# Circuit_comp.net
KiCad netlist of a schematic drawn in Altium Designer
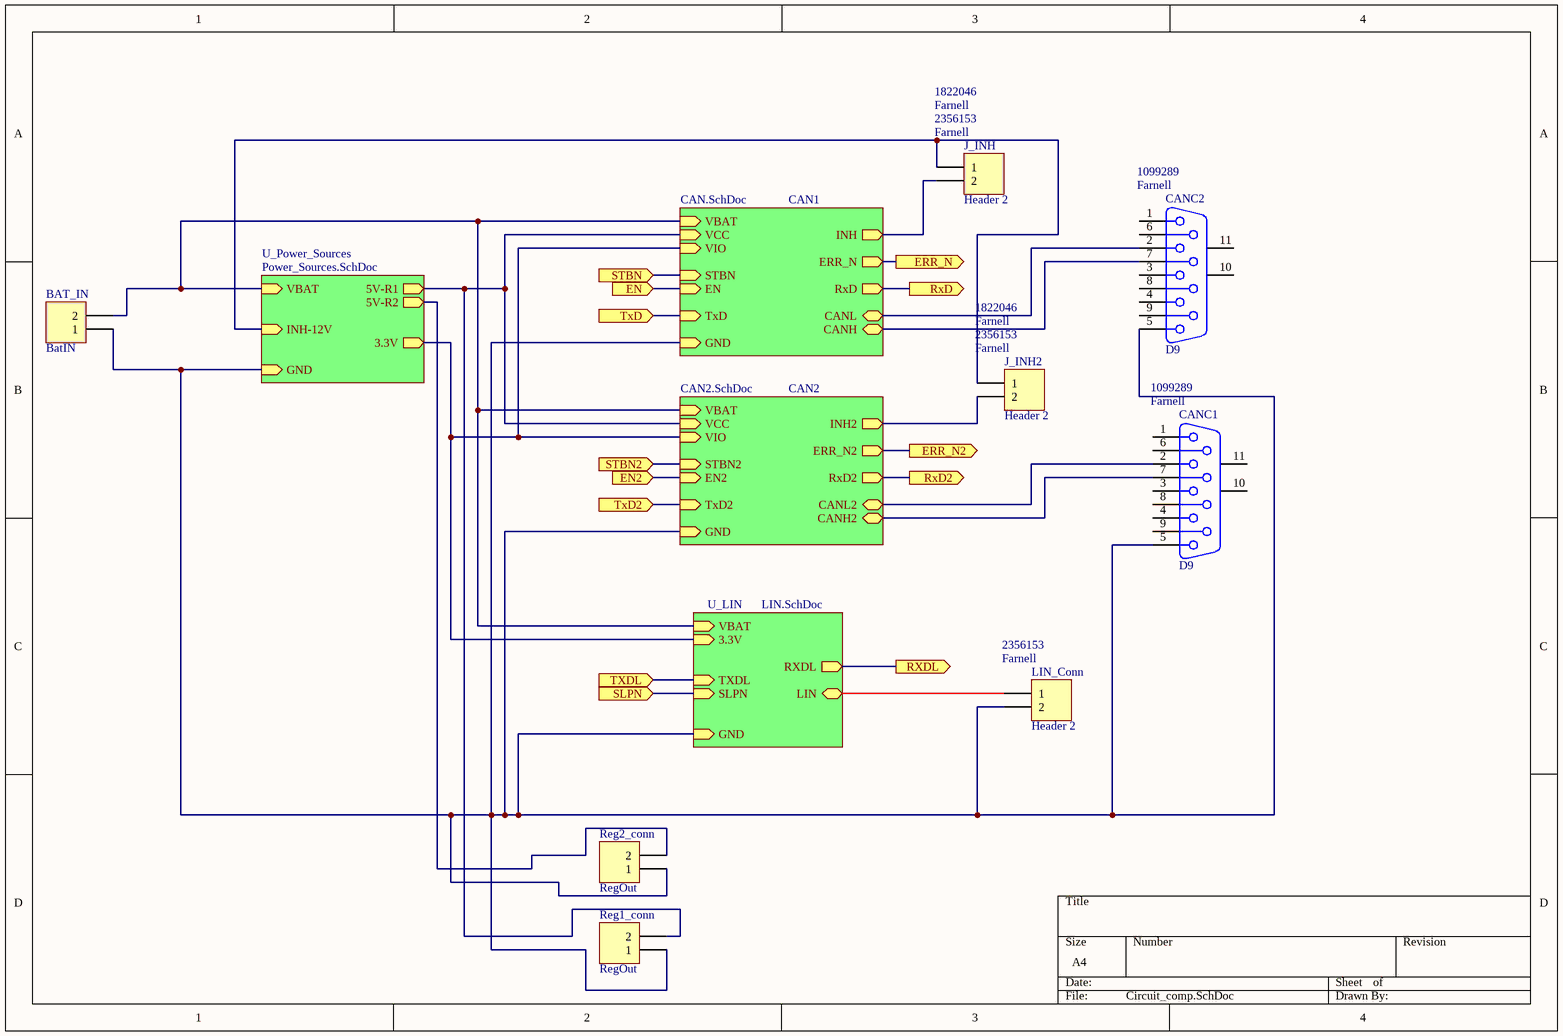
[diagram p0: Circuit_comp.SchDoc]

(export (version "E")
  (design (tool "Eeschema 10.0.6"))
  (components
    (comp (ref "BAT_IN")
      (value "BatIN")
      (footprint "HDR1X2")
      (description "Header, 2-Pin")
      (fields (field (name "PUBLISHER") "Altium Limited"))
      (libsource (lib "") (part "Header 2_1"))
    )
    (comp (ref "CANC1")
      (value "D9")
      (footprint "DSUB1.385-2H9")
      (description "Receptacle Assembly, 9 Position, Right Angle")
      (fields
        (field (name "SUPPLIER 1") "Farnell")
        (field (name "SUPPLIER PART NUMBER 1") "1099289")
        (field (name "PUBLISHER") "Altium Limited")
      )
      (libsource (lib "Miscellaneous Connectors") (part "D Connector 9"))
    )
    (comp (ref "CANC2")
      (value "D9")
      (footprint "DSUB1.385-2H9")
      (description "Receptacle Assembly, 9 Position, Right Angle")
      (fields
        (field (name "SUPPLIER 1") "Farnell")
        (field (name "SUPPLIER PART NUMBER 1") "1099289")
        (field (name "PUBLISHER") "Altium Limited")
      )
      (libsource (lib "Miscellaneous Connectors") (part "D Connector 9"))
    )
    (comp (ref "J_INH")
      (value "Header 2")
      (footprint "HDR1X2")
      (description "Header, 2-Pin")
      (fields
        (field (name "SUPPLIER 1") "Farnell")
        (field (name "SUPPLIER PART NUMBER 1") "2356153")
        (field (name "SUPPLIER 2") "Farnell")
        (field (name "SUPPLIER PART NUMBER 2") "1822046")
        (field (name "PUBLISHER") "Altium Limited")
      )
      (libsource (lib "Miscellaneous Connectors") (part "Header 2"))
    )
    (comp (ref "J_INH2")
      (value "Header 2")
      (footprint "HDR1X2")
      (description "Header, 2-Pin")
      (fields
        (field (name "SUPPLIER 1") "Farnell")
        (field (name "SUPPLIER PART NUMBER 1") "2356153")
        (field (name "SUPPLIER 2") "Farnell")
        (field (name "SUPPLIER PART NUMBER 2") "1822046")
        (field (name "PUBLISHER") "Altium Limited")
      )
      (libsource (lib "Miscellaneous Connectors") (part "Header 2"))
    )
    (comp (ref "LIN_Conn")
      (value "Header 2")
      (footprint "HDR1X2")
      (description "Header, 2-Pin")
      (fields
        (field (name "SUPPLIER 1") "Farnell")
        (field (name "SUPPLIER PART NUMBER 1") "2356153")
        (field (name "PUBLISHER") "Altium Limited")
      )
      (libsource (lib "Miscellaneous Connectors") (part "Header 2"))
    )
    (comp (ref "Reg1_conn")
      (value "RegOut")
      (footprint "HDR1X2")
      (description "Header, 2-Pin")
      (fields (field (name "PUBLISHER") "Altium Limited"))
      (libsource (lib "") (part "Header 2_1"))
    )
    (comp (ref "Reg2_conn")
      (value "RegOut")
      (footprint "HDR1X2")
      (description "Header, 2-Pin")
      (fields (field (name "PUBLISHER") "Altium Limited"))
      (libsource (lib "") (part "Header 2_1"))
    )
  )
  (nets
    (net (code "2") (name "/5V-R1") (class "Default")
      (node (ref "Reg1_conn") (pin "2") (pinfunction "2_2") (pintype "passive"))
    )
    (net (code "3") (name "/5V-R2") (class "Default")
      (node (ref "Reg2_conn") (pin "2") (pinfunction "2_2") (pintype "passive"))
    )
    (net (code "4") (name "/CANH") (class "Default")
      (node (ref "CANC2") (pin "7") (pinfunction "7_7") (pintype "passive"))
    )
    (net (code "5") (name "/CANH2") (class "Default")
      (node (ref "CANC1") (pin "7") (pinfunction "7_7") (pintype "passive"))
    )
    (net (code "6") (name "/CANL") (class "Default")
      (node (ref "CANC2") (pin "2") (pinfunction "2_2") (pintype "passive"))
    )
    (net (code "7") (name "/CANL2") (class "Default")
      (node (ref "CANC1") (pin "2") (pinfunction "2_2") (pintype "passive"))
    )
    (net (code "12") (name "/GND") (class "Default")
      (node (ref "BAT_IN") (pin "1") (pinfunction "1_1") (pintype "passive"))
      (node (ref "CANC1") (pin "5") (pinfunction "5_5") (pintype "passive"))
      (node (ref "CANC2") (pin "5") (pinfunction "5_5") (pintype "passive"))
      (node (ref "LIN_Conn") (pin "2") (pinfunction "2_2") (pintype "passive"))
      (node (ref "Reg1_conn") (pin "1") (pinfunction "1_1") (pintype "passive"))
      (node (ref "Reg2_conn") (pin "1") (pinfunction "1_1") (pintype "passive"))
    )
    (net (code "13") (name "/INH") (class "Default")
      (node (ref "J_INH") (pin "2") (pinfunction "2_2") (pintype "passive"))
    )
    (net (code "14") (name "/INH-12V") (class "Default")
      (node (ref "J_INH") (pin "1") (pinfunction "1_1") (pintype "passive"))
      (node (ref "J_INH2") (pin "1") (pinfunction "1_1") (pintype "passive"))
    )
    (net (code "15") (name "/INH2") (class "Default")
      (node (ref "J_INH2") (pin "2") (pinfunction "2_2") (pintype "passive"))
    )
    (net (code "16") (name "/LIN") (class "Default")
      (node (ref "LIN_Conn") (pin "1") (pinfunction "1_1") (pintype "passive"))
    )
    (net (code "26") (name "/VBAT") (class "Default")
      (node (ref "BAT_IN") (pin "2") (pinfunction "2_2") (pintype "passive"))
    )
    (net (code "27") (name "unconnected-(CANC1-MH1-Pad10)") (class "Default")
      (node (ref "CANC1") (pin "10") (pinfunction "MH1_10") (pintype "passive"))
    )
    (net (code "28") (name "unconnected-(CANC1-MH2-Pad11)") (class "Default")
      (node (ref "CANC1") (pin "11") (pinfunction "MH2_11") (pintype "passive"))
    )
    (net (code "29") (name "unconnected-(CANC1-Pad1)") (class "Default")
      (node (ref "CANC1") (pin "1") (pinfunction "1_1") (pintype "passive"))
    )
    (net (code "30") (name "unconnected-(CANC1-Pad3)") (class "Default")
      (node (ref "CANC1") (pin "3") (pinfunction "3_3") (pintype "passive"))
    )
    (net (code "31") (name "unconnected-(CANC1-Pad4)") (class "Default")
      (node (ref "CANC1") (pin "4") (pinfunction "4_4") (pintype "passive"))
    )
    (net (code "32") (name "unconnected-(CANC1-Pad6)") (class "Default")
      (node (ref "CANC1") (pin "6") (pinfunction "6_6") (pintype "passive"))
    )
    (net (code "33") (name "unconnected-(CANC1-Pad8)") (class "Default")
      (node (ref "CANC1") (pin "8") (pinfunction "8_8") (pintype "passive"))
    )
    (net (code "34") (name "unconnected-(CANC1-Pad9)") (class "Default")
      (node (ref "CANC1") (pin "9") (pinfunction "9_9") (pintype "passive"))
    )
    (net (code "35") (name "unconnected-(CANC2-MH1-Pad10)") (class "Default")
      (node (ref "CANC2") (pin "10") (pinfunction "MH1_10") (pintype "passive"))
    )
    (net (code "36") (name "unconnected-(CANC2-MH2-Pad11)") (class "Default")
      (node (ref "CANC2") (pin "11") (pinfunction "MH2_11") (pintype "passive"))
    )
    (net (code "37") (name "unconnected-(CANC2-Pad1)") (class "Default")
      (node (ref "CANC2") (pin "1") (pinfunction "1_1") (pintype "passive"))
    )
    (net (code "38") (name "unconnected-(CANC2-Pad3)") (class "Default")
      (node (ref "CANC2") (pin "3") (pinfunction "3_3") (pintype "passive"))
    )
    (net (code "39") (name "unconnected-(CANC2-Pad4)") (class "Default")
      (node (ref "CANC2") (pin "4") (pinfunction "4_4") (pintype "passive"))
    )
    (net (code "40") (name "unconnected-(CANC2-Pad6)") (class "Default")
      (node (ref "CANC2") (pin "6") (pinfunction "6_6") (pintype "passive"))
    )
    (net (code "41") (name "unconnected-(CANC2-Pad8)") (class "Default")
      (node (ref "CANC2") (pin "8") (pinfunction "8_8") (pintype "passive"))
    )
    (net (code "42") (name "unconnected-(CANC2-Pad9)") (class "Default")
      (node (ref "CANC2") (pin "9") (pinfunction "9_9") (pintype "passive"))
    )
  )
)
